# Micro.net
KiCad netlist of a schematic drawn in Altium Designer
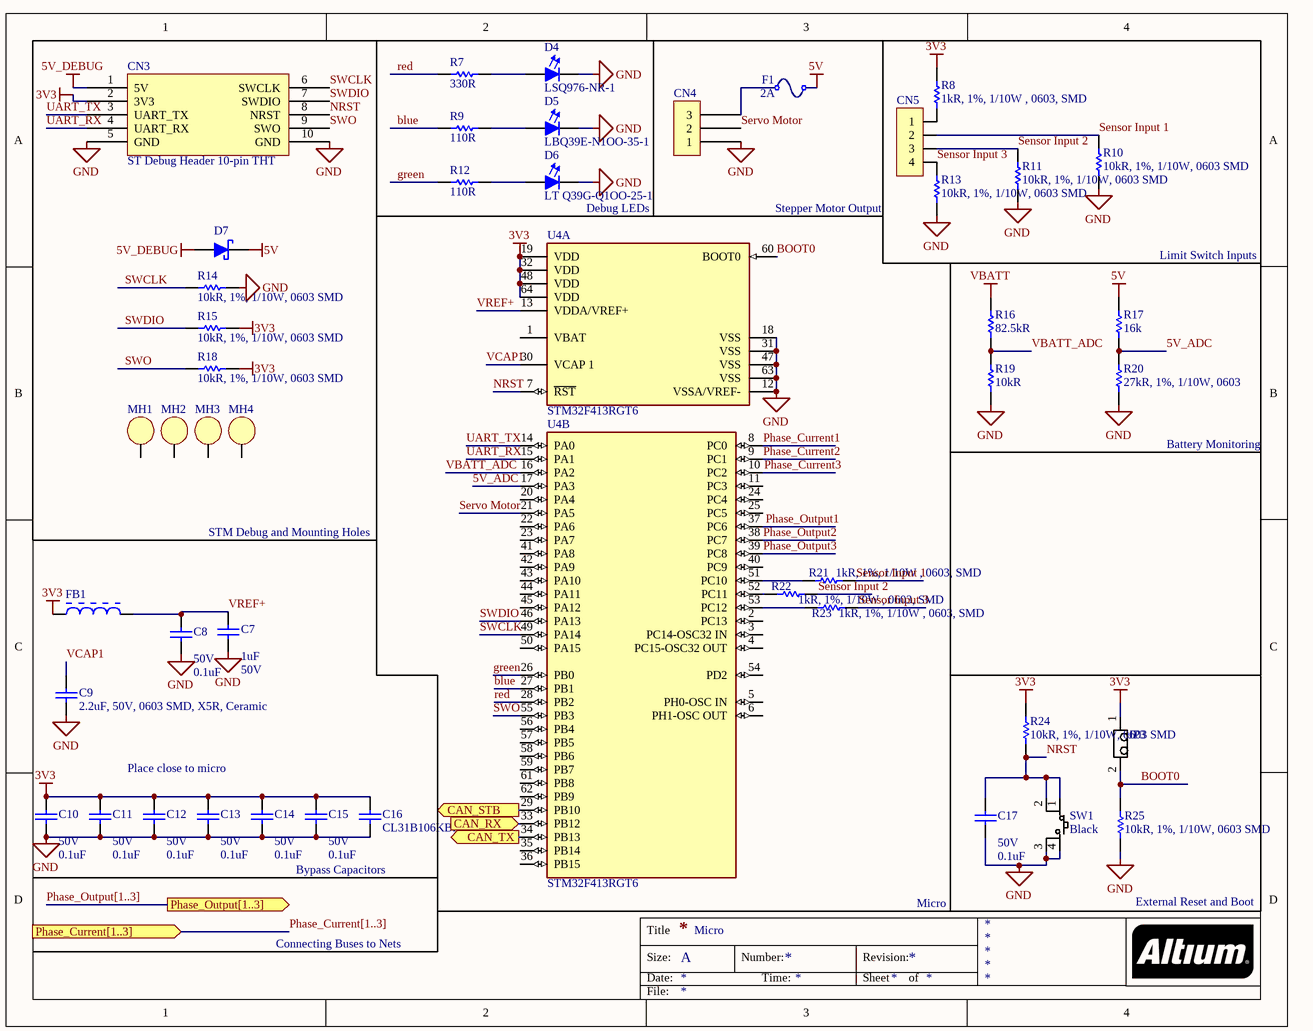
[diagram p0: Micro.SchDoc]

(export (version "E")
  (design (tool "Eeschema 10.0.6"))
  (components
    (comp (ref "C7")
      (value "CL21B105KBFNNNG")
      (footprint "0803 CAP")
      (description "SAMSUNG ELECTRO-MECHANICS - CL21B105KBFNNNG - MLCC CAPACITORS")
      (fields
        (field (name "TOLERANCE") "10%")
        (field (name "CAPACITANCE") "1uF")
        (field (name "VOLTAGE") "50V")
      )
      (libsource (lib "") (part "Symbol_7"))
    )
    (comp (ref "C8")
      (value "CL10B104JB8NNNC")
      (footprint "FP-CL10-0_1-IPC_A")
      (description "CAP CER 0.1UF 50V X7R 0603")
      (fields
        (field (name "TOLERANCE") "5%")
        (field (name "VOLTAGE") "50V")
        (field (name "CAPACITANCE") "0.1uF")
      )
      (libsource (lib "AUVIC") (part "CAP-NP-2"))
    )
    (comp (ref "C9")
      (value "2.2uF, 50V, 0603 SMD, X5R, Ceramic")
      (footprint "CAPC1608N(0603\")")
      (description "Capacitor, Ceramic, 50V, 10%, 0603 SMD, X5R")
      (fields (field (name "MADE BY") "*") (field (name "PUBLISHER") "AUVic"))
      (libsource (lib "AUVIC") (part "Symbol"))
    )
    (comp (ref "C10")
      (value "CL10B104JB8NNNC")
      (footprint "FP-CL10-0_1-IPC_A")
      (description "CAP CER 0.1UF 50V X7R 0603")
      (fields
        (field (name "TOLERANCE") "5%")
        (field (name "VOLTAGE") "50V")
        (field (name "CAPACITANCE") "0.1uF")
      )
      (libsource (lib "AUVIC") (part "CAP-NP-2"))
    )
    (comp (ref "C11")
      (value "CL10B104JB8NNNC")
      (footprint "FP-CL10-0_1-IPC_A")
      (description "CAP CER 0.1UF 50V X7R 0603")
      (fields
        (field (name "TOLERANCE") "5%")
        (field (name "VOLTAGE") "50V")
        (field (name "CAPACITANCE") "0.1uF")
      )
      (libsource (lib "AUVIC") (part "CAP-NP-2"))
    )
    (comp (ref "C12")
      (value "CL10B104JB8NNNC")
      (footprint "FP-CL10-0_1-IPC_A")
      (description "CAP CER 0.1UF 50V X7R 0603")
      (fields
        (field (name "TOLERANCE") "5%")
        (field (name "VOLTAGE") "50V")
        (field (name "CAPACITANCE") "0.1uF")
      )
      (libsource (lib "AUVIC") (part "CAP-NP-2"))
    )
    (comp (ref "C13")
      (value "CL10B104JB8NNNC")
      (footprint "FP-CL10-0_1-IPC_A")
      (description "CAP CER 0.1UF 50V X7R 0603")
      (fields
        (field (name "TOLERANCE") "5%")
        (field (name "VOLTAGE") "50V")
        (field (name "CAPACITANCE") "0.1uF")
      )
      (libsource (lib "AUVIC") (part "CAP-NP-2"))
    )
    (comp (ref "C14")
      (value "CL10B104JB8NNNC")
      (footprint "FP-CL10-0_1-IPC_A")
      (description "CAP CER 0.1UF 50V X7R 0603")
      (fields
        (field (name "TOLERANCE") "5%")
        (field (name "VOLTAGE") "50V")
        (field (name "CAPACITANCE") "0.1uF")
      )
      (libsource (lib "AUVIC") (part "CAP-NP-2"))
    )
    (comp (ref "C15")
      (value "CL10B104JB8NNNC")
      (footprint "FP-CL10-0_1-IPC_A")
      (description "CAP CER 0.1UF 50V X7R 0603")
      (fields
        (field (name "TOLERANCE") "5%")
        (field (name "VOLTAGE") "50V")
        (field (name "CAPACITANCE") "0.1uF")
      )
      (libsource (lib "AUVIC") (part "CAP-NP-2"))
    )
    (comp (ref "C16")
      (value "CL31B106KBHNNNE")
      (footprint "CAPC3216X180X50ML20T30")
      (description "Cap Ceramic 10uF 50V X7R 10% Pad SMD 1206 125°C T/R")
      (fields (field (name "TOLERANCE") "10%"))
      (libsource (lib "AUVIC") (part "CAP-NP-2"))
    )
    (comp (ref "C17")
      (value "CL10B104JB8NNNC")
      (footprint "FP-CL10-0_1-IPC_A")
      (description "CAP CER 0.1UF 50V X7R 0603")
      (fields
        (field (name "TOLERANCE") "5%")
        (field (name "VOLTAGE") "50V")
        (field (name "CAPACITANCE") "0.1uF")
      )
      (libsource (lib "AUVIC") (part "CAP-NP-2"))
    )
    (comp (ref "CN3")
      (value "ST Debug Header 10-pin THT")
      (footprint "10-pin shrouded header THT")
      (description "CONN HEADER VERT 10POS 2.54MM")
      (libsource (lib "AUVIC") (part "ST Debug Header 10-pin"))
    )
    (comp (ref "CN4")
      (value "Header, Male, 1x3, RA, Pitch (2.54mm) 0.1\"")
      (footprint "5-103635-2-Footprint-1")
      (description "CONN HEADER RT/A .100 3POS 15AU")
      (libsource (lib "AUVIC") (part "5-103635-2"))
    )
    (comp (ref "CN5")
      (value "Header, Male, 1x4, RA, Pitch 0.1\" (2.54mm)")
      (footprint "HEADER, MALE, SHROUDED, 4x1, PITCH 0.1\" (2.54mm), RA")
      (description "Connector Header Through Hole, Right Angle 4 position 0.100\" (2.54mm)")
      (fields (field (name "CREATED BY") "Miguel Manguerra"))
      (libsource (lib "") (part "Symbol_6"))
    )
    (comp (ref "D4")
      (value "LSQ976-NR-1")
      (footprint "FP-LB_Q39E-MFG")
      (description "LED Red 645nm 2-Pin Chip 0603(1608Metric) T/R")
      (libsource (lib "") (part "Symbol_4"))
    )
    (comp (ref "D5")
      (value "LBQ39E-N1OO-35-1")
      (footprint "FP-LB_Q39E-MFG")
      (description "LED BLUE DIFFUSED 0603 SMD")
      (libsource (lib "") (part "Symbol_4"))
    )
    (comp (ref "D6")
      (value "LT Q39G-Q1OO-25-1")
      (footprint "FP-LB_Q39E-MFG")
      (description "LED GREEN DIFFUSED 0603 SMD")
      (libsource (lib "") (part "Symbol_4"))
    )
    (comp (ref "D7")
      (value "CUS08F30,H3F")
      (footprint "SC-76")
      (description "Diode Schottky 30V 800mA Surface Mount USC")
      (libsource (lib "") (part "Symbol_3"))
    )
    (comp (ref "F1")
      (value "SMD Fuse, 2A, 63V,")
      (footprint "1206 SMD")
      (fields (field (name "CURRENT") "2A") (field (name "CREATED BY") "Poorna Chander Kalidas"))
      (libsource (lib "") (part "Symbol_1"))
    )
    (comp (ref "FB1")
      (value "BLM18AG601SN1D")
      (footprint "MURA-BLM18-F-H1-CHIP-2_V")
      (fields (field (name "TOLERANCE") "25%"))
      (libsource (lib "AUVIC") (part "MURA-FB-2"))
    )
    (comp (ref "JP3")
      (value "1x2 Male Header")
      (footprint "2X1 Males Header")
      (fields (field (name "MADE BY") "Andy Bates"))
      (libsource (lib "AUVIC") (part "1x2 Male Header"))
    )
    (comp (ref "MH1")
      (value "Mount_Hole_3mm")
      (footprint "Mount-Hole_3mm")
      (description "Mounting hold for M3 hex standoff")
      (libsource (lib "AUVIC") (part "Mount_Hole_3mm"))
    )
    (comp (ref "MH2")
      (value "Mount_Hole_3mm")
      (footprint "Mount-Hole_3mm")
      (description "Mounting hold for M3 hex standoff")
      (libsource (lib "AUVIC") (part "Mount_Hole_3mm"))
    )
    (comp (ref "MH3")
      (value "Mount_Hole_3mm")
      (footprint "Mount-Hole_3mm")
      (description "Mounting hold for M3 hex standoff")
      (libsource (lib "AUVIC") (part "Mount_Hole_3mm"))
    )
    (comp (ref "MH4")
      (value "Mount_Hole_3mm")
      (footprint "Mount-Hole_3mm")
      (description "Mounting hold for M3 hex standoff")
      (libsource (lib "AUVIC") (part "Mount_Hole_3mm"))
    )
    (comp (ref "R7")
      (value "CRCW0603330RFKEA")
      (footprint "FP-CRCW0603-e3-IPC_A")
      (description "Res Thick Film 0603 330 Ohm 1% 0.1W(1/10W) +/-100ppm/ßC Pad SMD Automotive T/R")
      (fields (field (name "TOLERANCE") "1%") (field (name "RESISTANCE") "330R"))
      (libsource (lib "AUVIC") (part "RES"))
    )
    (comp (ref "R8")
      (value "1kR, 1%, 1/10W , 0603, SMD")
      (footprint "RESC1608N(0603\")")
      (fields (field (name "PUBLISHER") "AUVic") (field (name "CREATED BY") "Andy Bates"))
      (libsource (lib "") (part "Symbol_2"))
    )
    (comp (ref "R9")
      (value "RC0603FR-07110RL")
      (footprint "RESC1608X55X25ML10T15")
      (description "RES SMD 110 OHM 1% 1/10W 0603")
      (fields (field (name "TOLERANCE") "1%") (field (name "RESISTANCE") "110R"))
      (libsource (lib "AUVIC") (part "RES"))
    )
    (comp (ref "R10")
      (value "10kR, 1%, 1/10W, 0603 SMD")
      (footprint "RESC1608N(0603\")")
      (fields (field (name "MADE BY") "Ashwin Sira"))
      (libsource (lib "") (part "Symbol_2"))
    )
    (comp (ref "R11")
      (value "10kR, 1%, 1/10W, 0603 SMD")
      (footprint "RESC1608N(0603\")")
      (fields (field (name "MADE BY") "Ashwin Sira"))
      (libsource (lib "") (part "Symbol_2"))
    )
    (comp (ref "R12")
      (value "RC0603FR-07110RL")
      (footprint "RESC1608X55X25ML10T15")
      (description "RES SMD 110 OHM 1% 1/10W 0603")
      (fields (field (name "TOLERANCE") "1%") (field (name "RESISTANCE") "110R"))
      (libsource (lib "AUVIC") (part "RES"))
    )
    (comp (ref "R13")
      (value "10kR, 1%, 1/10W, 0603 SMD")
      (footprint "RESC1608N(0603\")")
      (fields (field (name "MADE BY") "Ashwin Sira"))
      (libsource (lib "") (part "Symbol_2"))
    )
    (comp (ref "R14")
      (value "10kR, 1%, 1/10W, 0603 SMD")
      (footprint "RESC1608N(0603\")")
      (fields (field (name "MADE BY") "Ashwin Sira"))
      (libsource (lib "") (part "Symbol_2"))
    )
    (comp (ref "R15")
      (value "10kR, 1%, 1/10W, 0603 SMD")
      (footprint "RESC1608N(0603\")")
      (fields (field (name "MADE BY") "Ashwin Sira"))
      (libsource (lib "") (part "Symbol_2"))
    )
    (comp (ref "R16")
      (value "ERJ-3EKF8252V")
      (footprint "RESC1608X55X30ML15T15")
      (description "RES SMD 82.5K OHM 1% 1/10W 0603")
      (fields (field (name "RESISTANCE") "82.5kR") (field (name "TOLERANCE") "1%"))
      (libsource (lib "AUVIC") (part "RES"))
    )
    (comp (ref "R17")
      (value "16k")
      (footprint "RESC1608N(0603\")")
      (description "16kR, 1%, 1/10W, 0603 SMD")
      (fields (field (name "MADE BY") "Ashwin Sira"))
      (libsource (lib "") (part "Symbol_2"))
    )
    (comp (ref "R18")
      (value "10kR, 1%, 1/10W, 0603 SMD")
      (footprint "RESC1608N(0603\")")
      (fields (field (name "MADE BY") "Ashwin Sira"))
      (libsource (lib "") (part "Symbol_2"))
    )
    (comp (ref "R19")
      (value "RC0603FR-0710KL")
      (footprint "RESC1608X55X25ML10T15")
      (description "Res General Purpose Thick Film 0603 10K Ohm 1% 1/10W ±100ppm/°C Molded SMD Paper T/R")
      (fields (field (name "RESISTANCE") "10kR") (field (name "TOLERANCE") "1%"))
      (libsource (lib "AUVIC") (part "RES-2"))
    )
    (comp (ref "R20")
      (value "27kR, 1%, 1/10W, 0603")
      (footprint "FP-CRGCQ0603-IPC_B")
      (description "Res Thick Film 0603 27K Ohm 1% 0.1W(1/10W) ±100ppm/C Pad SMD Automotive T/R")
      (libsource (lib "AUVIC") (part "RES"))
    )
    (comp (ref "R21")
      (value "1kR, 1%, 1/10W , 0603, SMD")
      (footprint "RESC1608N(0603\")")
      (fields (field (name "PUBLISHER") "AUVic") (field (name "CREATED BY") "Andy Bates"))
      (libsource (lib "") (part "Symbol_2"))
    )
    (comp (ref "R22")
      (value "1kR, 1%, 1/10W , 0603, SMD")
      (footprint "RESC1608N(0603\")")
      (fields (field (name "PUBLISHER") "AUVic") (field (name "CREATED BY") "Andy Bates"))
      (libsource (lib "") (part "Symbol_2"))
    )
    (comp (ref "R23")
      (value "1kR, 1%, 1/10W , 0603, SMD")
      (footprint "RESC1608N(0603\")")
      (fields (field (name "PUBLISHER") "AUVic") (field (name "CREATED BY") "Andy Bates"))
      (libsource (lib "") (part "Symbol_2"))
    )
    (comp (ref "R24")
      (value "10kR, 1%, 1/10W, 0603 SMD")
      (footprint "RESC1608N(0603\")")
      (fields (field (name "MADE BY") "Ashwin Sira"))
      (libsource (lib "") (part "Symbol_2"))
    )
    (comp (ref "R25")
      (value "10kR, 1%, 1/10W, 0603 SMD")
      (footprint "RESC1608N(0603\")")
      (fields (field (name "MADE BY") "Ashwin Sira"))
      (libsource (lib "") (part "Symbol_2"))
    )
    (comp (ref "SW1")
      (value "PTS645SL43SMTR92LFS")
      (footprint "4-SPST-NO")
      (description "Black Switch Tactile N.O. SPST Round Button Gull Wing 0.05A 12VDC 100000Cycles 1.27N SMD T/R")
      (fields (field (name "BUTTON COLOUR") "Black"))
      (libsource (lib "") (part "Symbol_5"))
    )
    (comp (ref "U4")
      (value "STM32F413RGT6")
      (footprint "FP-LQFP64-5W-IPC_A")
      (description "STMICROELECTRONICS - STM32F413RGT6 - MCU, ARM CORTEX-M4, 100MHZ, LQFP-64")
      (libsource (lib "AUVIC") (part "7f3deadac312a1e532344b4e443717e"))
    )
  )
  (nets
    (net (code "1") (name "/5V_ADC") (class "Default")
      (node (ref "R17") (pin "1") (pinfunction "1_1") (pintype "passive"))
      (node (ref "R20") (pin "2") (pinfunction "2_2") (pintype "passive"))
      (node (ref "U4") (pin "17") (pinfunction "PA3_17") (pintype "bidirectional"))
    )
    (net (code "2") (name "/BOOT0") (class "Default")
      (node (ref "JP3") (pin "2") (pinfunction "2_2") (pintype "passive"))
      (node (ref "R25") (pin "1") (pinfunction "1_1") (pintype "passive"))
      (node (ref "U4") (pin "60") (pinfunction "BOOT0_60") (pintype "input"))
    )
    (net (code "3") (name "/CAN_RX") (class "Default")
      (node (ref "U4") (pin "33") (pinfunction "PB12_33") (pintype "bidirectional"))
    )
    (net (code "4") (name "/CAN_STB") (class "Default")
      (node (ref "U4") (pin "29") (pinfunction "PB10_29") (pintype "bidirectional"))
    )
    (net (code "5") (name "/CAN_TX") (class "Default")
      (node (ref "U4") (pin "34") (pinfunction "PB13_34") (pintype "bidirectional"))
    )
    (net (code "6") (name "/NRST") (class "Default")
      (node (ref "C17") (pin "1") (pinfunction "1_1") (pintype "passive"))
      (node (ref "CN3") (pin "8") (pinfunction "NRST_8") (pintype "passive"))
      (node (ref "R24") (pin "2") (pinfunction "2_2") (pintype "passive"))
      (node (ref "SW1") (pin "1") (pinfunction "1_1") (pintype "passive"))
      (node (ref "SW1") (pin "2") (pinfunction "2_2") (pintype "passive"))
      (node (ref "U4") (pin "7") (pinfunction "~{RST}_7") (pintype "bidirectional"))
    )
    (net (code "7") (name "/Phase_Current1") (class "Default")
      (node (ref "U4") (pin "8") (pinfunction "PC0_8") (pintype "bidirectional"))
    )
    (net (code "8") (name "/Phase_Current2") (class "Default")
      (node (ref "U4") (pin "9") (pinfunction "PC1_9") (pintype "bidirectional"))
    )
    (net (code "9") (name "/Phase_Current3") (class "Default")
      (node (ref "U4") (pin "10") (pinfunction "PC2_10") (pintype "bidirectional"))
    )
    (net (code "11") (name "/Phase_Output1") (class "Default")
      (node (ref "U4") (pin "37") (pinfunction "PC6_37") (pintype "bidirectional"))
    )
    (net (code "12") (name "/Phase_Output2") (class "Default")
      (node (ref "U4") (pin "38") (pinfunction "PC7_38") (pintype "bidirectional"))
    )
    (net (code "13") (name "/Phase_Output3") (class "Default")
      (node (ref "U4") (pin "39") (pinfunction "PC8_39") (pintype "bidirectional"))
    )
    (net (code "15") (name "/SWCLK") (class "Default")
      (node (ref "CN3") (pin "6") (pinfunction "SWCLK_6") (pintype "passive"))
      (node (ref "R14") (pin "2") (pinfunction "2_2") (pintype "passive"))
      (node (ref "U4") (pin "49") (pinfunction "PA14_49") (pintype "bidirectional"))
    )
    (net (code "16") (name "/SWDIO") (class "Default")
      (node (ref "CN3") (pin "7") (pinfunction "SWDIO_7") (pintype "passive"))
      (node (ref "R15") (pin "2") (pinfunction "2_2") (pintype "passive"))
      (node (ref "U4") (pin "46") (pinfunction "PA13_46") (pintype "bidirectional"))
    )
    (net (code "17") (name "/SWO") (class "Default")
      (node (ref "CN3") (pin "9") (pinfunction "SWO_9") (pintype "passive"))
      (node (ref "R18") (pin "2") (pinfunction "2_2") (pintype "passive"))
      (node (ref "U4") (pin "55") (pinfunction "PB3_55") (pintype "bidirectional"))
    )
    (net (code "18") (name "/Sensor Input 1") (class "Default")
      (node (ref "CN5") (pin "2") (pinfunction "2_2") (pintype "passive"))
      (node (ref "R10") (pin "1") (pinfunction "1_1") (pintype "passive"))
      (node (ref "R21") (pin "2") (pinfunction "2_2") (pintype "passive"))
    )
    (net (code "19") (name "/Sensor Input 2") (class "Default")
      (node (ref "CN5") (pin "3") (pinfunction "3_3") (pintype "passive"))
      (node (ref "R11") (pin "1") (pinfunction "1_1") (pintype "passive"))
      (node (ref "R22") (pin "2") (pinfunction "2_2") (pintype "passive"))
    )
    (net (code "20") (name "/Sensor Input 3") (class "Default")
      (node (ref "CN5") (pin "4") (pinfunction "4_4") (pintype "passive"))
      (node (ref "R13") (pin "1") (pinfunction "1_1") (pintype "passive"))
      (node (ref "R23") (pin "2") (pinfunction "2_2") (pintype "passive"))
    )
    (net (code "21") (name "/Servo Motor") (class "Default")
      (node (ref "CN4") (pin "2") (pinfunction "2_2") (pintype "power_in"))
      (node (ref "U4") (pin "21") (pinfunction "PA5_21") (pintype "bidirectional"))
    )
    (net (code "22") (name "/UART_RX") (class "Default")
      (node (ref "CN3") (pin "4") (pinfunction "UART_RX_4") (pintype "passive"))
      (node (ref "U4") (pin "15") (pinfunction "PA1_15") (pintype "bidirectional"))
    )
    (net (code "23") (name "/UART_TX") (class "Default")
      (node (ref "CN3") (pin "3") (pinfunction "UART_TX_3") (pintype "passive"))
      (node (ref "U4") (pin "14") (pinfunction "PA0_14") (pintype "bidirectional"))
    )
    (net (code "24") (name "/VBATT_ADC") (class "Default")
      (node (ref "R16") (pin "2") (pinfunction "2_2") (pintype "passive"))
      (node (ref "R19") (pin "1") (pinfunction "1_1") (pintype "passive"))
      (node (ref "U4") (pin "16") (pinfunction "PA2_16") (pintype "bidirectional"))
    )
    (net (code "25") (name "/VCAP1") (class "Default")
      (node (ref "C9") (pin "1") (pinfunction "Anode_1") (pintype "passive"))
      (node (ref "U4") (pin "30") (pinfunction "VCAP_1_30") (pintype "power_in"))
    )
    (net (code "26") (name "/VREF+") (class "Default")
      (node (ref "C7") (pin "1") (pinfunction "1_1") (pintype "passive"))
      (node (ref "C8") (pin "1") (pinfunction "1_1") (pintype "passive"))
      (node (ref "FB1") (pin "2") (pinfunction "2_2") (pintype "passive"))
      (node (ref "U4") (pin "13") (pinfunction "VDDA/VREF+_13") (pintype "power_in"))
    )
    (net (code "27") (name "/blue") (class "Default")
      (node (ref "R9") (pin "1") (pinfunction "1_1") (pintype "passive"))
      (node (ref "U4") (pin "27") (pinfunction "PB1_27") (pintype "bidirectional"))
    )
    (net (code "28") (name "/green") (class "Default")
      (node (ref "R12") (pin "1") (pinfunction "1_1") (pintype "passive"))
      (node (ref "U4") (pin "26") (pinfunction "PB0_26") (pintype "bidirectional"))
    )
    (net (code "29") (name "/red") (class "Default")
      (node (ref "R7") (pin "1") (pinfunction "1_1") (pintype "passive"))
      (node (ref "U4") (pin "28") (pinfunction "PB2_28") (pintype "bidirectional"))
    )
    (net (code "30") (name "3V3") (class "Default")
      (node (ref "C10") (pin "1") (pinfunction "1_1") (pintype "passive"))
      (node (ref "C11") (pin "1") (pinfunction "1_1") (pintype "passive"))
      (node (ref "C12") (pin "1") (pinfunction "1_1") (pintype "passive"))
      (node (ref "C13") (pin "1") (pinfunction "1_1") (pintype "passive"))
      (node (ref "C14") (pin "1") (pinfunction "1_1") (pintype "passive"))
      (node (ref "C15") (pin "1") (pinfunction "1_1") (pintype "passive"))
      (node (ref "C16") (pin "1") (pinfunction "1_1") (pintype "passive"))
      (node (ref "CN3") (pin "2") (pinfunction "3V3_2") (pintype "passive"))
      (node (ref "FB1") (pin "1") (pinfunction "1_1") (pintype "passive"))
      (node (ref "JP3") (pin "1") (pinfunction "1_1") (pintype "passive"))
      (node (ref "R15") (pin "1") (pinfunction "1_1") (pintype "passive"))
      (node (ref "R18") (pin "1") (pinfunction "1_1") (pintype "passive"))
      (node (ref "R24") (pin "1") (pinfunction "1_1") (pintype "passive"))
      (node (ref "R8") (pin "1") (pinfunction "1_1") (pintype "passive"))
      (node (ref "U4") (pin "19") (pinfunction "VDD_19") (pintype "power_in"))
      (node (ref "U4") (pin "32") (pinfunction "VDD_32") (pintype "power_in"))
      (node (ref "U4") (pin "48") (pinfunction "VDD_48") (pintype "power_in"))
      (node (ref "U4") (pin "64") (pinfunction "VDD_64") (pintype "power_in"))
    )
    (net (code "31") (name "5V") (class "Default")
      (node (ref "D7") (pin "K") (pinfunction "Cathode_K") (pintype "passive"))
      (node (ref "F1") (pin "2") (pinfunction "2_2") (pintype "passive"))
      (node (ref "R17") (pin "2") (pinfunction "2_2") (pintype "passive"))
    )
    (net (code "32") (name "5V_DEBUG") (class "Default")
      (node (ref "CN3") (pin "1") (pinfunction "5V_1") (pintype "passive"))
      (node (ref "D7") (pin "A") (pinfunction "Anode_A") (pintype "passive"))
    )
    (net (code "33") (name "GND") (class "Default")
      (node (ref "C10") (pin "2") (pinfunction "2_2") (pintype "passive"))
      (node (ref "C11") (pin "2") (pinfunction "2_2") (pintype "passive"))
      (node (ref "C12") (pin "2") (pinfunction "2_2") (pintype "passive"))
      (node (ref "C13") (pin "2") (pinfunction "2_2") (pintype "passive"))
      (node (ref "C14") (pin "2") (pinfunction "2_2") (pintype "passive"))
      (node (ref "C15") (pin "2") (pinfunction "2_2") (pintype "passive"))
      (node (ref "C16") (pin "2") (pinfunction "2_2") (pintype "passive"))
      (node (ref "C17") (pin "2") (pinfunction "2_2") (pintype "passive"))
      (node (ref "C7") (pin "2") (pinfunction "2_2") (pintype "passive"))
      (node (ref "C8") (pin "2") (pinfunction "2_2") (pintype "passive"))
      (node (ref "C9") (pin "2") (pinfunction "Cathode_2") (pintype "passive"))
      (node (ref "CN3") (pin "10") (pinfunction "GND_10") (pintype "passive"))
      (node (ref "CN3") (pin "5") (pinfunction "GND_5") (pintype "passive"))
      (node (ref "CN4") (pin "1") (pinfunction "1_1") (pintype "power_in"))
      (node (ref "D4") (pin "1") (pinfunction "Cathode_1") (pintype "passive"))
      (node (ref "D5") (pin "1") (pinfunction "Cathode_1") (pintype "passive"))
      (node (ref "D6") (pin "1") (pinfunction "Cathode_1") (pintype "passive"))
      (node (ref "R10") (pin "2") (pinfunction "2_2") (pintype "passive"))
      (node (ref "R11") (pin "2") (pinfunction "2_2") (pintype "passive"))
      (node (ref "R13") (pin "2") (pinfunction "2_2") (pintype "passive"))
      (node (ref "R14") (pin "1") (pinfunction "1_1") (pintype "passive"))
      (node (ref "R19") (pin "2") (pinfunction "2_2") (pintype "passive"))
      (node (ref "R20") (pin "1") (pinfunction "1_1") (pintype "passive"))
      (node (ref "R25") (pin "2") (pinfunction "2_2") (pintype "passive"))
      (node (ref "SW1") (pin "3") (pinfunction "3_3") (pintype "passive"))
      (node (ref "SW1") (pin "4") (pinfunction "4_4") (pintype "passive"))
      (node (ref "U4") (pin "12") (pinfunction "VSSA/VREF-_12") (pintype "power_in"))
      (node (ref "U4") (pin "18") (pinfunction "VSS_18") (pintype "power_in"))
      (node (ref "U4") (pin "31") (pinfunction "VSS_31") (pintype "power_in"))
      (node (ref "U4") (pin "47") (pinfunction "VSS_47") (pintype "power_in"))
      (node (ref "U4") (pin "63") (pinfunction "VSS_63") (pintype "power_in"))
    )
    (net (code "34") (name "Net-(CN4-Pad3)") (class "Default")
      (node (ref "CN4") (pin "3") (pinfunction "3_3") (pintype "power_in"))
      (node (ref "F1") (pin "1") (pinfunction "1_1") (pintype "passive"))
    )
    (net (code "35") (name "Net-(CN5-Pad1)") (class "Default")
      (node (ref "CN5") (pin "1") (pinfunction "1_1") (pintype "passive"))
      (node (ref "R8") (pin "2") (pinfunction "2_2") (pintype "passive"))
    )
    (net (code "36") (name "Net-(D4-Anode)") (class "Default")
      (node (ref "D4") (pin "2") (pinfunction "Anode_2") (pintype "passive"))
      (node (ref "R7") (pin "2") (pinfunction "2_2") (pintype "passive"))
    )
    (net (code "37") (name "Net-(D5-Anode)") (class "Default")
      (node (ref "D5") (pin "2") (pinfunction "Anode_2") (pintype "passive"))
      (node (ref "R9") (pin "2") (pinfunction "2_2") (pintype "passive"))
    )
    (net (code "38") (name "Net-(D6-Anode)") (class "Default")
      (node (ref "D6") (pin "2") (pinfunction "Anode_2") (pintype "passive"))
      (node (ref "R12") (pin "2") (pinfunction "2_2") (pintype "passive"))
    )
    (net (code "39") (name "Net-(U4B-PC10)") (class "Default")
      (node (ref "R21") (pin "1") (pinfunction "1_1") (pintype "passive"))
      (node (ref "U4") (pin "51") (pinfunction "PC10_51") (pintype "bidirectional"))
    )
    (net (code "40") (name "Net-(U4B-PC11)") (class "Default")
      (node (ref "R22") (pin "1") (pinfunction "1_1") (pintype "passive"))
      (node (ref "U4") (pin "52") (pinfunction "PC11_52") (pintype "bidirectional"))
    )
    (net (code "41") (name "Net-(U4B-PC12)") (class "Default")
      (node (ref "R23") (pin "1") (pinfunction "1_1") (pintype "passive"))
      (node (ref "U4") (pin "53") (pinfunction "PC12_53") (pintype "bidirectional"))
    )
    (net (code "42") (name "VBATT") (class "Default")
      (node (ref "R16") (pin "1") (pinfunction "1_1") (pintype "passive"))
    )
    (net (code "43") (name "unconnected-(MH1-Pad1)") (class "Default")
      (node (ref "MH1") (pin "1") (pinfunction "1_1") (pintype "passive"))
    )
    (net (code "44") (name "unconnected-(MH2-Pad1)") (class "Default")
      (node (ref "MH2") (pin "1") (pinfunction "1_1") (pintype "passive"))
    )
    (net (code "45") (name "unconnected-(MH3-Pad1)") (class "Default")
      (node (ref "MH3") (pin "1") (pinfunction "1_1") (pintype "passive"))
    )
    (net (code "46") (name "unconnected-(MH4-Pad1)") (class "Default")
      (node (ref "MH4") (pin "1") (pinfunction "1_1") (pintype "passive"))
    )
    (net (code "47") (name "unconnected-(U4A-VBAT-Pad1)") (class "Default")
      (node (ref "U4") (pin "1") (pinfunction "VBAT_1") (pintype "power_in"))
    )
    (net (code "48") (name "unconnected-(U4B-PA4-Pad20)") (class "Default")
      (node (ref "U4") (pin "20") (pinfunction "PA4_20") (pintype "bidirectional"))
    )
    (net (code "49") (name "unconnected-(U4B-PA6-Pad22)") (class "Default")
      (node (ref "U4") (pin "22") (pinfunction "PA6_22") (pintype "bidirectional"))
    )
    (net (code "50") (name "unconnected-(U4B-PA7-Pad23)") (class "Default")
      (node (ref "U4") (pin "23") (pinfunction "PA7_23") (pintype "bidirectional"))
    )
    (net (code "51") (name "unconnected-(U4B-PA8-Pad41)") (class "Default")
      (node (ref "U4") (pin "41") (pinfunction "PA8_41") (pintype "bidirectional"))
    )
    (net (code "52") (name "unconnected-(U4B-PA9-Pad42)") (class "Default")
      (node (ref "U4") (pin "42") (pinfunction "PA9_42") (pintype "bidirectional"))
    )
    (net (code "53") (name "unconnected-(U4B-PA10-Pad43)") (class "Default")
      (node (ref "U4") (pin "43") (pinfunction "PA10_43") (pintype "bidirectional"))
    )
    (net (code "54") (name "unconnected-(U4B-PA11-Pad44)") (class "Default")
      (node (ref "U4") (pin "44") (pinfunction "PA11_44") (pintype "bidirectional"))
    )
    (net (code "55") (name "unconnected-(U4B-PA12-Pad45)") (class "Default")
      (node (ref "U4") (pin "45") (pinfunction "PA12_45") (pintype "bidirectional"))
    )
    (net (code "56") (name "unconnected-(U4B-PA15-Pad50)") (class "Default")
      (node (ref "U4") (pin "50") (pinfunction "PA15_50") (pintype "bidirectional"))
    )
    (net (code "57") (name "unconnected-(U4B-PB4-Pad56)") (class "Default")
      (node (ref "U4") (pin "56") (pinfunction "PB4_56") (pintype "bidirectional"))
    )
    (net (code "58") (name "unconnected-(U4B-PB5-Pad57)") (class "Default")
      (node (ref "U4") (pin "57") (pinfunction "PB5_57") (pintype "bidirectional"))
    )
    (net (code "59") (name "unconnected-(U4B-PB6-Pad58)") (class "Default")
      (node (ref "U4") (pin "58") (pinfunction "PB6_58") (pintype "bidirectional"))
    )
    (net (code "60") (name "unconnected-(U4B-PB7-Pad59)") (class "Default")
      (node (ref "U4") (pin "59") (pinfunction "PB7_59") (pintype "bidirectional"))
    )
    (net (code "61") (name "unconnected-(U4B-PB8-Pad61)") (class "Default")
      (node (ref "U4") (pin "61") (pinfunction "PB8_61") (pintype "bidirectional"))
    )
    (net (code "62") (name "unconnected-(U4B-PB9-Pad62)") (class "Default")
      (node (ref "U4") (pin "62") (pinfunction "PB9_62") (pintype "bidirectional"))
    )
    (net (code "63") (name "unconnected-(U4B-PB14-Pad35)") (class "Default")
      (node (ref "U4") (pin "35") (pinfunction "PB14_35") (pintype "bidirectional"))
    )
    (net (code "64") (name "unconnected-(U4B-PB15-Pad36)") (class "Default")
      (node (ref "U4") (pin "36") (pinfunction "PB15_36") (pintype "bidirectional"))
    )
    (net (code "65") (name "unconnected-(U4B-PC3-Pad11)") (class "Default")
      (node (ref "U4") (pin "11") (pinfunction "PC3_11") (pintype "bidirectional"))
    )
    (net (code "66") (name "unconnected-(U4B-PC4-Pad24)") (class "Default")
      (node (ref "U4") (pin "24") (pinfunction "PC4_24") (pintype "bidirectional"))
    )
    (net (code "67") (name "unconnected-(U4B-PC5-Pad25)") (class "Default")
      (node (ref "U4") (pin "25") (pinfunction "PC5_25") (pintype "bidirectional"))
    )
    (net (code "68") (name "unconnected-(U4B-PC9-Pad40)") (class "Default")
      (node (ref "U4") (pin "40") (pinfunction "PC9_40") (pintype "bidirectional"))
    )
    (net (code "69") (name "unconnected-(U4B-PC13-Pad2)") (class "Default")
      (node (ref "U4") (pin "2") (pinfunction "PC13_2") (pintype "bidirectional"))
    )
    (net (code "70") (name "unconnected-(U4B-PC14-OSC32_IN-Pad3)") (class "Default")
      (node (ref "U4") (pin "3") (pinfunction "PC14-OSC32_IN_3") (pintype "bidirectional"))
    )
    (net (code "71") (name "unconnected-(U4B-PC15-OSC32_OUT-Pad4)") (class "Default")
      (node (ref "U4") (pin "4") (pinfunction "PC15-OSC32_OUT_4") (pintype "bidirectional"))
    )
    (net (code "72") (name "unconnected-(U4B-PD2-Pad54)") (class "Default")
      (node (ref "U4") (pin "54") (pinfunction "PD2_54") (pintype "bidirectional"))
    )
    (net (code "73") (name "unconnected-(U4B-PH0-OSC_IN-Pad5)") (class "Default")
      (node (ref "U4") (pin "5") (pinfunction "PH0-OSC_IN_5") (pintype "bidirectional"))
    )
    (net (code "74") (name "unconnected-(U4B-PH1-OSC_OUT-Pad6)") (class "Default")
      (node (ref "U4") (pin "6") (pinfunction "PH1-OSC_OUT_6") (pintype "bidirectional"))
    )
  )
)
